# Module.net
KiCad netlist of a schematic drawn in Altium Designer
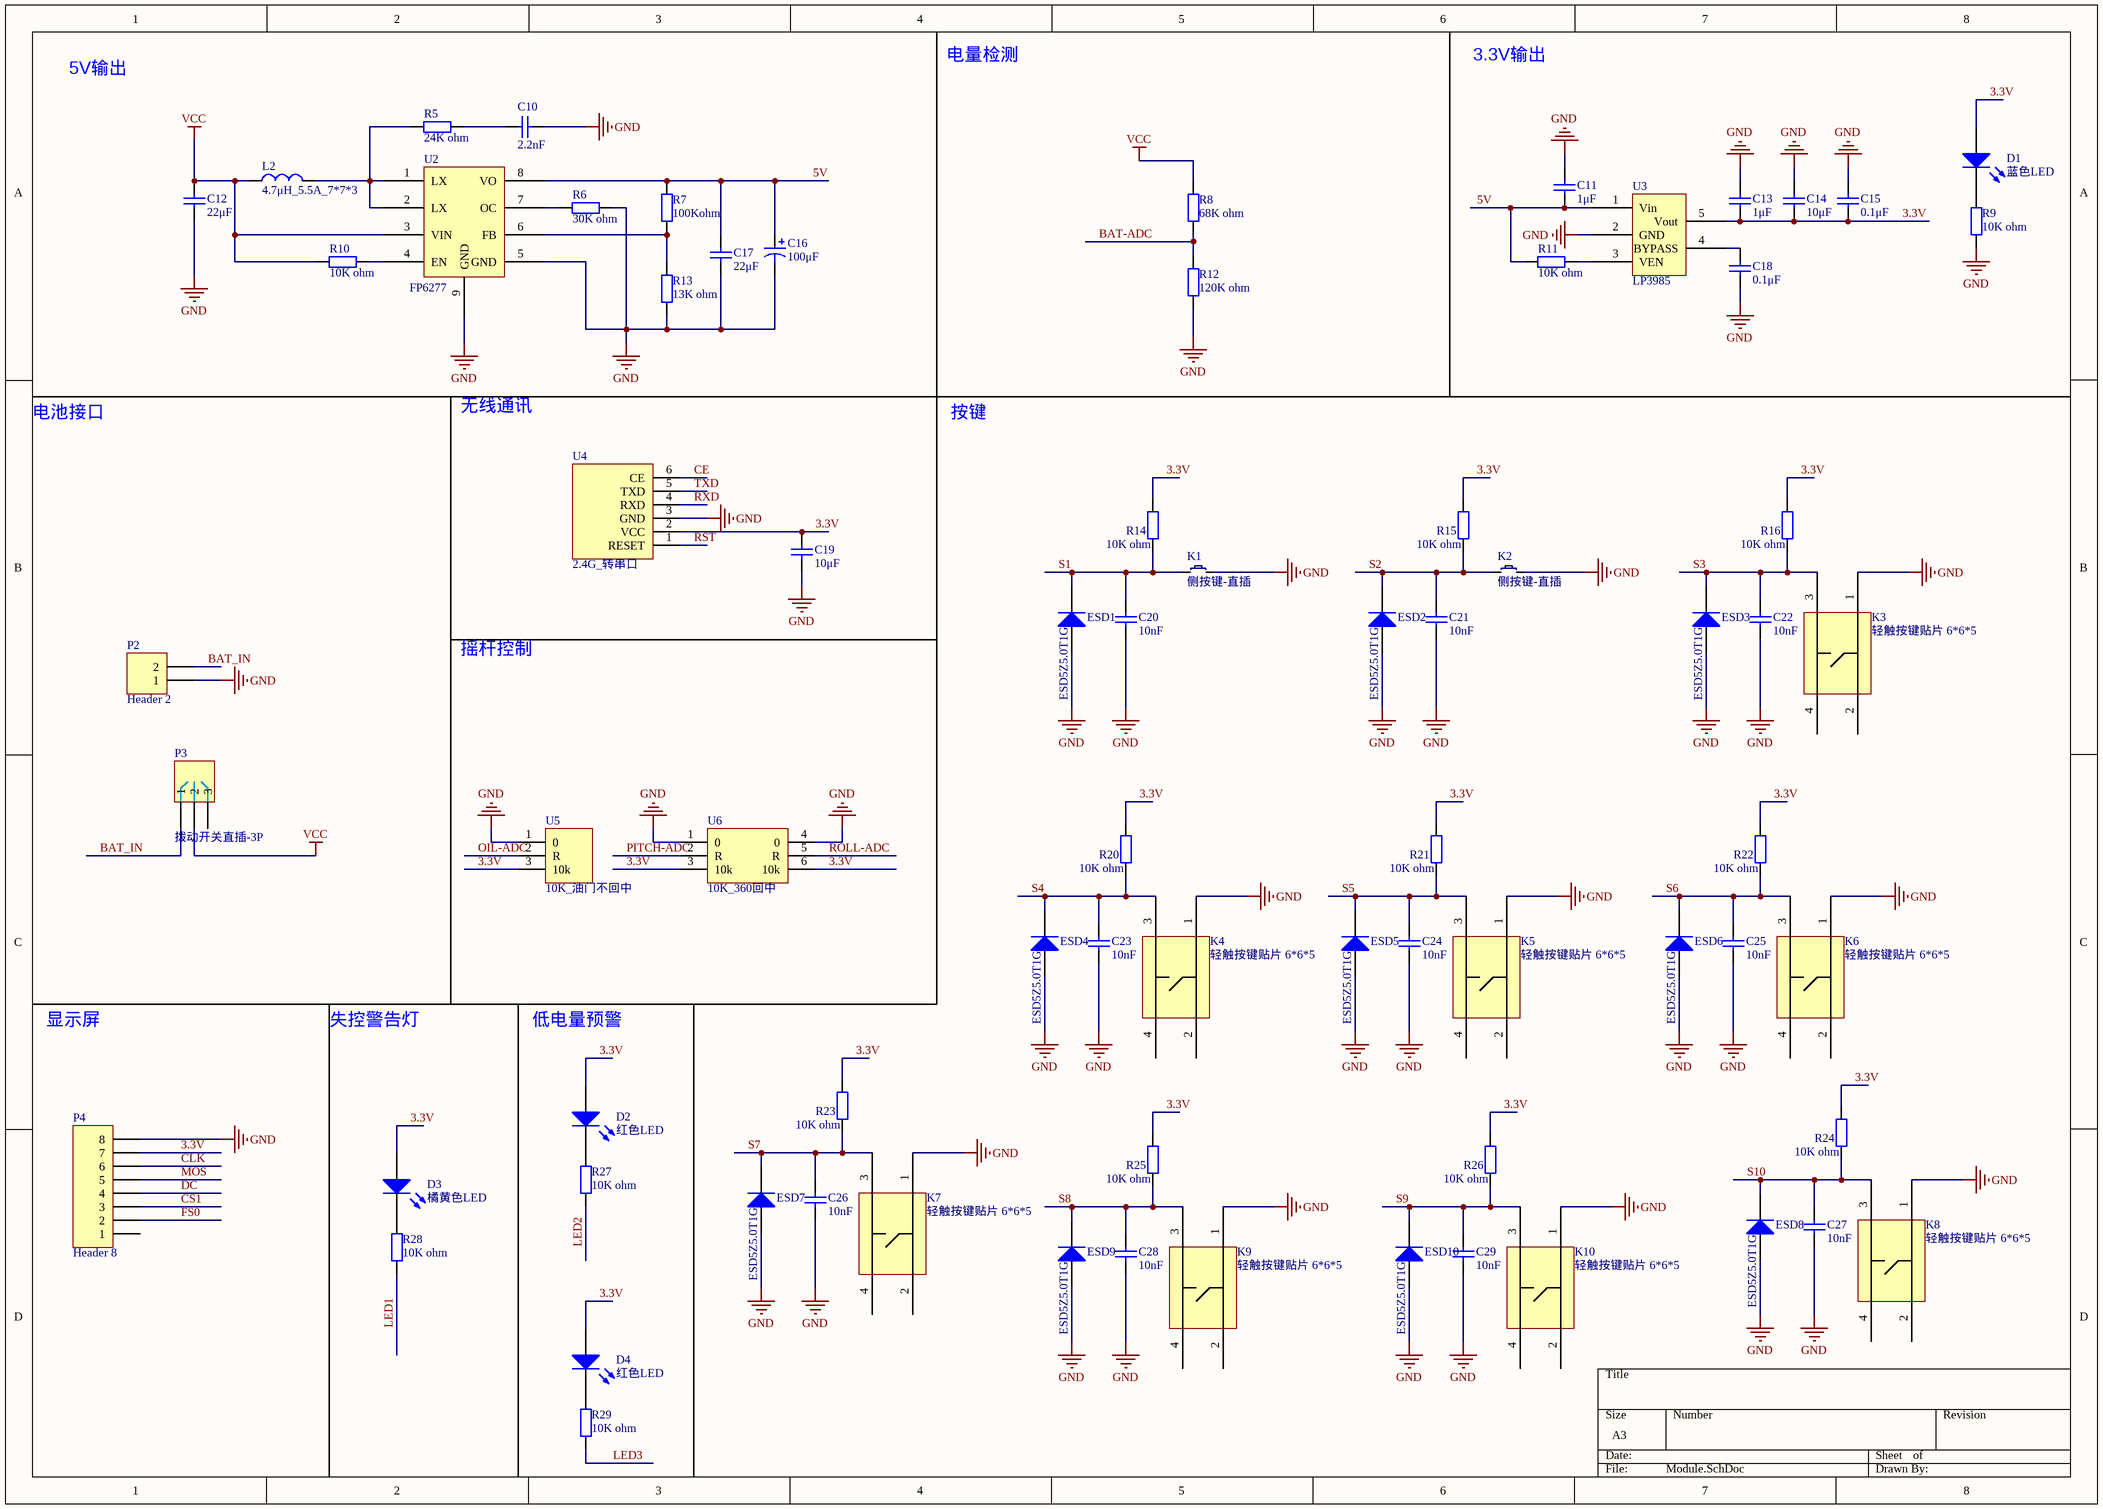
[diagram p0: Module.SchDoc]

(export (version "E")
  (design (tool "Eeschema 10.0.6"))
  (components
    (comp (ref "C10")
      (value "2.2nF")
      (footprint "0603C")
      (description "2.2nF_50V,X7R,10%")
      (libsource (lib "Yang_Lib") (part "Cap_2.2nF_50V_0603"))
    )
    (comp (ref "C11")
      (value "1μF")
      (footprint "0603C")
      (description "1μF_50V,X5R,±10%")
      (libsource (lib "Yang_Lib") (part "Cap_1μF_50V_0603"))
    )
    (comp (ref "C12")
      (value "22μF")
      (footprint "1206C")
      (description "22μF_35V,20%")
      (libsource (lib "Yang_Lib") (part "Cap_22μF_35V_1206"))
    )
    (comp (ref "C13")
      (value "1μF")
      (footprint "0603C")
      (description "1μF_50V,X5R,±10%")
      (libsource (lib "Yang_Lib") (part "Cap_1μF_50V_0603"))
    )
    (comp (ref "C14")
      (value "10μF")
      (footprint "0603C")
      (description "10μF_35V,X5R,20%")
      (libsource (lib "Yang_Lib") (part "Cap_10μF_35V_0603"))
    )
    (comp (ref "C15")
      (value "0.1μF")
      (footprint "0603C")
      (description "0.1μF_50V,X7R,±5%")
      (libsource (lib "Yang_Lib") (part "Cap_0.1μF_50V_0603"))
    )
    (comp (ref "C16")
      (value "100μF")
      (footprint "D7343C")
      (description "100μF_16V")
      (libsource (lib "Yang_Lib") (part "Cap_100μF_16V_D7343"))
    )
    (comp (ref "C17")
      (value "22μF")
      (footprint "1206C")
      (description "22μF_35V,20%")
      (libsource (lib "Yang_Lib") (part "Cap_22μF_35V_1206"))
    )
    (comp (ref "C18")
      (value "0.1μF")
      (footprint "0603C")
      (description "0.1μF_50V,X7R,±5%")
      (libsource (lib "Yang_Lib") (part "Cap_0.1μF_50V_0603"))
    )
    (comp (ref "C19")
      (value "10μF")
      (footprint "0603C")
      (description "10μF_35V,X5R,20%")
      (libsource (lib "Yang_Lib") (part "Cap_10μF_35V_0603"))
    )
    (comp (ref "C20")
      (value "10nF")
      (footprint "0603C")
      (description "10nF_50V,SL_0603,±5%")
      (libsource (lib "Yang_Lib") (part "Cap_10nF_50V_0603"))
    )
    (comp (ref "C21")
      (value "10nF")
      (footprint "0603C")
      (description "10nF_50V,SL_0603,±5%")
      (libsource (lib "Yang_Lib") (part "Cap_10nF_50V_0603"))
    )
    (comp (ref "C22")
      (value "10nF")
      (footprint "0603C")
      (description "10nF_50V,SL_0603,±5%")
      (libsource (lib "Yang_Lib") (part "Cap_10nF_50V_0603"))
    )
    (comp (ref "C23")
      (value "10nF")
      (footprint "0603C")
      (description "10nF_50V,SL_0603,±5%")
      (libsource (lib "Yang_Lib") (part "Cap_10nF_50V_0603"))
    )
    (comp (ref "C24")
      (value "10nF")
      (footprint "0603C")
      (description "10nF_50V,SL_0603,±5%")
      (libsource (lib "Yang_Lib") (part "Cap_10nF_50V_0603"))
    )
    (comp (ref "C25")
      (value "10nF")
      (footprint "0603C")
      (description "10nF_50V,SL_0603,±5%")
      (libsource (lib "Yang_Lib") (part "Cap_10nF_50V_0603"))
    )
    (comp (ref "C26")
      (value "10nF")
      (footprint "0603C")
      (description "10nF_50V,SL_0603,±5%")
      (libsource (lib "Yang_Lib") (part "Cap_10nF_50V_0603"))
    )
    (comp (ref "C27")
      (value "10nF")
      (footprint "0603C")
      (description "10nF_50V,SL_0603,±5%")
      (libsource (lib "Yang_Lib") (part "Cap_10nF_50V_0603"))
    )
    (comp (ref "C28")
      (value "10nF")
      (footprint "0603C")
      (description "10nF_50V,SL_0603,±5%")
      (libsource (lib "Yang_Lib") (part "Cap_10nF_50V_0603"))
    )
    (comp (ref "C29")
      (value "10nF")
      (footprint "0603C")
      (description "10nF_50V,SL_0603,±5%")
      (libsource (lib "Yang_Lib") (part "Cap_10nF_50V_0603"))
    )
    (comp (ref "D1")
      (value "蓝色LED")
      (footprint "Yang_Lib:0603LED")
      (libsource (lib "FSR_BodyLib") (part "蓝色LED"))
    )
    (comp (ref "D2")
      (value "红色LED")
      (footprint "Yang_Lib:0603LED")
      (description "蓝色LED")
      (libsource (lib "FSR_BodyLib") (part "蓝色LED"))
    )
    (comp (ref "D3")
      (value "橘黄色LED")
      (footprint "Yang_Lib:0603LED")
      (description "蓝色LED")
      (libsource (lib "FSR_BodyLib") (part "蓝色LED"))
    )
    (comp (ref "D4")
      (value "红色LED")
      (footprint "Yang_Lib:0603LED")
      (description "蓝色LED")
      (libsource (lib "FSR_BodyLib") (part "蓝色LED"))
    )
    (comp (ref "ESD1")
      (value "ESD5Z5.0T1G")
      (footprint "SOD523")
      (libsource (lib "Yang_Lib") (part "ESD5Z5.0T1G_SOD523"))
    )
    (comp (ref "ESD2")
      (value "ESD5Z5.0T1G")
      (footprint "SOD523")
      (libsource (lib "Yang_Lib") (part "ESD5Z5.0T1G_SOD523"))
    )
    (comp (ref "ESD3")
      (value "ESD5Z5.0T1G")
      (footprint "SOD523")
      (libsource (lib "Yang_Lib") (part "ESD5Z5.0T1G_SOD523"))
    )
    (comp (ref "ESD4")
      (value "ESD5Z5.0T1G")
      (footprint "SOD523")
      (libsource (lib "Yang_Lib") (part "ESD5Z5.0T1G_SOD523"))
    )
    (comp (ref "ESD5")
      (value "ESD5Z5.0T1G")
      (footprint "SOD523")
      (libsource (lib "Yang_Lib") (part "ESD5Z5.0T1G_SOD523"))
    )
    (comp (ref "ESD6")
      (value "ESD5Z5.0T1G")
      (footprint "SOD523")
      (libsource (lib "Yang_Lib") (part "ESD5Z5.0T1G_SOD523"))
    )
    (comp (ref "ESD7")
      (value "ESD5Z5.0T1G")
      (footprint "SOD523")
      (libsource (lib "Yang_Lib") (part "ESD5Z5.0T1G_SOD523"))
    )
    (comp (ref "ESD8")
      (value "ESD5Z5.0T1G")
      (footprint "SOD523")
      (libsource (lib "Yang_Lib") (part "ESD5Z5.0T1G_SOD523"))
    )
    (comp (ref "ESD9")
      (value "ESD5Z5.0T1G")
      (footprint "SOD523")
      (libsource (lib "Yang_Lib") (part "ESD5Z5.0T1G_SOD523"))
    )
    (comp (ref "ESD10")
      (value "ESD5Z5.0T1G")
      (footprint "SOD523")
      (libsource (lib "Yang_Lib") (part "ESD5Z5.0T1G_SOD523"))
    )
    (comp (ref "K1") (value "侧按键-直插") (footprint "侧按键-直插") (libsource (lib "Yang_Lib") (part "侧按键-直插")))
    (comp (ref "K2") (value "侧按键-直插") (footprint "侧按键-直插") (libsource (lib "Yang_Lib") (part "侧按键-直插")))
    (comp (ref "K3")
      (value "轻触按键贴片 6*6*5")
      (footprint "轻触按键贴片 6*6*5")
      (libsource (lib "Yang_Lib") (part "轻触按键贴片 6*6*5"))
    )
    (comp (ref "K4")
      (value "轻触按键贴片 6*6*5")
      (footprint "轻触按键贴片 6*6*5")
      (libsource (lib "Yang_Lib") (part "轻触按键贴片 6*6*5"))
    )
    (comp (ref "K5")
      (value "轻触按键贴片 6*6*5")
      (footprint "轻触按键贴片 6*6*5")
      (libsource (lib "Yang_Lib") (part "轻触按键贴片 6*6*5"))
    )
    (comp (ref "K6")
      (value "轻触按键贴片 6*6*5")
      (footprint "轻触按键贴片 6*6*5")
      (libsource (lib "Yang_Lib") (part "轻触按键贴片 6*6*5"))
    )
    (comp (ref "K7")
      (value "轻触按键贴片 6*6*5")
      (footprint "轻触按键贴片 6*6*5")
      (libsource (lib "Yang_Lib") (part "轻触按键贴片 6*6*5"))
    )
    (comp (ref "K8")
      (value "轻触按键贴片 6*6*5")
      (footprint "轻触按键贴片 6*6*5")
      (libsource (lib "Yang_Lib") (part "轻触按键贴片 6*6*5"))
    )
    (comp (ref "K9")
      (value "轻触按键贴片 6*6*5")
      (footprint "轻触按键贴片 6*6*5")
      (libsource (lib "Yang_Lib") (part "轻触按键贴片 6*6*5"))
    )
    (comp (ref "K10")
      (value "轻触按键贴片 6*6*5")
      (footprint "轻触按键贴片 6*6*5")
      (libsource (lib "Yang_Lib") (part "轻触按键贴片 6*6*5"))
    )
    (comp (ref "L2")
      (value "4.7μH_5.5A_7*7*3")
      (footprint "7*7*3mm - 06030")
      (description "4.7μH_5.5A_")
      (libsource (lib "Yang_Lib") (part "4.7μH_5.5A_7*7*3"))
    )
    (comp (ref "P2")
      (value "Header 2")
      (footprint "HDR1X2")
      (description "Header, 2-Pin")
      (fields (field (name "PUBLISHER") "Altium Limited"))
      (libsource (lib "Miscellaneous Connectors") (part "Header 2"))
    )
    (comp (ref "P3")
      (value "拨动开关直插-3P")
      (footprint "拨动开关-3P")
      (libsource (lib "Yang_Lib") (part "拨动开关直插-3P"))
    )
    (comp (ref "P4")
      (value "Header 8")
      (footprint "HDR1X8")
      (description "Header, 8-Pin")
      (fields (field (name "PUBLISHER") "Altium Limited"))
      (libsource (lib "Miscellaneous Connectors") (part "Header 8"))
    )
    (comp (ref "R5")
      (value "24K ohm")
      (footprint "0603R")
      (description "24K ohm,1%")
      (libsource (lib "Yang_Lib") (part "Res_24K ohm_0603"))
    )
    (comp (ref "R6")
      (value "30K ohm")
      (footprint "0603R")
      (description "30K ohm,1%")
      (libsource (lib "Yang_Lib") (part "Res_30K ohm_0603"))
    )
    (comp (ref "R7")
      (value "100Kohm")
      (footprint "0603R")
      (description "100K ohm_5%")
      (libsource (lib "Yang_Lib") (part "Res_100Kohm_0603"))
    )
    (comp (ref "R8")
      (value "68K ohm")
      (footprint "0603R")
      (description "68K ohm,1%")
      (libsource (lib "Yang_Lib") (part "Res_68K ohm_0603"))
    )
    (comp (ref "R9")
      (value "10K ohm")
      (footprint "Yang_Lib:0603R")
      (description "10K ohm,1%")
      (libsource (lib "FSR_BodyLib") (part "Res_10K ohm_0603"))
    )
    (comp (ref "R10")
      (value "10K ohm")
      (footprint "0603R")
      (description "10K ohm,1%")
      (libsource (lib "Yang_Lib") (part "Res_10K ohm_0603"))
    )
    (comp (ref "R11")
      (value "10K ohm")
      (footprint "0603R")
      (description "10K ohm,1%")
      (libsource (lib "Yang_Lib") (part "Res_10K ohm_0603"))
    )
    (comp (ref "R12")
      (value "120K ohm")
      (footprint "0603R")
      (description "120K ohm,1%")
      (libsource (lib "Yang_Lib") (part "Res_120K ohm_0603"))
    )
    (comp (ref "R13")
      (value "13K ohm")
      (footprint "0603R")
      (description "13K ohm,1%")
      (libsource (lib "Yang_Lib") (part "Res_13K ohm_0603"))
    )
    (comp (ref "R14")
      (value "10K ohm")
      (footprint "0603R")
      (description "10K ohm,1%")
      (libsource (lib "") (part "Res_10K ohm_0603_1"))
    )
    (comp (ref "R15")
      (value "10K ohm")
      (footprint "0603R")
      (description "10K ohm,1%")
      (libsource (lib "") (part "Res_10K ohm_0603_1"))
    )
    (comp (ref "R16")
      (value "10K ohm")
      (footprint "0603R")
      (description "10K ohm,1%")
      (libsource (lib "") (part "Res_10K ohm_0603_1"))
    )
    (comp (ref "R20")
      (value "10K ohm")
      (footprint "0603R")
      (description "10K ohm,1%")
      (libsource (lib "") (part "Res_10K ohm_0603_1"))
    )
    (comp (ref "R21")
      (value "10K ohm")
      (footprint "0603R")
      (description "10K ohm,1%")
      (libsource (lib "") (part "Res_10K ohm_0603_1"))
    )
    (comp (ref "R22")
      (value "10K ohm")
      (footprint "0603R")
      (description "10K ohm,1%")
      (libsource (lib "") (part "Res_10K ohm_0603_1"))
    )
    (comp (ref "R23")
      (value "10K ohm")
      (footprint "0603R")
      (description "10K ohm,1%")
      (libsource (lib "") (part "Res_10K ohm_0603_1"))
    )
    (comp (ref "R24")
      (value "10K ohm")
      (footprint "0603R")
      (description "10K ohm,1%")
      (libsource (lib "") (part "Res_10K ohm_0603_1"))
    )
    (comp (ref "R25")
      (value "10K ohm")
      (footprint "0603R")
      (description "10K ohm,1%")
      (libsource (lib "") (part "Res_10K ohm_0603_1"))
    )
    (comp (ref "R26")
      (value "10K ohm")
      (footprint "0603R")
      (description "10K ohm,1%")
      (libsource (lib "") (part "Res_10K ohm_0603_1"))
    )
    (comp (ref "R27")
      (value "10K ohm")
      (footprint "Yang_Lib:0603R")
      (description "10K ohm,1%")
      (libsource (lib "FSR_BodyLib") (part "Res_10K ohm_0603"))
    )
    (comp (ref "R28")
      (value "10K ohm")
      (footprint "Yang_Lib:0603R")
      (description "10K ohm,1%")
      (libsource (lib "FSR_BodyLib") (part "Res_10K ohm_0603"))
    )
    (comp (ref "R29")
      (value "10K ohm")
      (footprint "Yang_Lib:0603R")
      (description "10K ohm,1%")
      (libsource (lib "FSR_BodyLib") (part "Res_10K ohm_0603"))
    )
    (comp (ref "U2") (value "FP6277") (footprint "SO8 - FP6277") (libsource (lib "Yang_Lib") (part "FP6277")))
    (comp (ref "U3") (value "LP3985") (footprint "SOT-23-5") (libsource (lib "Yang_Lib") (part "LP3985")))
    (comp (ref "U4") (value "2.4G_转串口") (footprint "2.4G-串口") (libsource (lib "Yang_Lib") (part "2.4G_转串口")))
    (comp (ref "U5")
      (value "10K_油门不回中")
      (footprint "10K_油门不回中")
      (libsource (lib "Yang_Lib") (part "10K_油门不回中"))
    )
    (comp (ref "U6")
      (value "10K_360回中")
      (footprint "10K_360回中")
      (libsource (lib "Yang_Lib") (part "10K_360回中"))
    )
  )
  (nets
    (net (code "1") (name "/3.3V") (class "Default")
      (node (ref "C13") (pin "2") (pinfunction "2_2") (pintype "passive"))
      (node (ref "C14") (pin "1") (pinfunction "1_1") (pintype "passive"))
      (node (ref "C15") (pin "1") (pinfunction "1_1") (pintype "passive"))
      (node (ref "C19") (pin "2") (pinfunction "2_2") (pintype "passive"))
      (node (ref "D1") (pin "1") (pinfunction "A_1") (pintype "passive"))
      (node (ref "D2") (pin "1") (pinfunction "A_1") (pintype "passive"))
      (node (ref "D3") (pin "1") (pinfunction "A_1") (pintype "passive"))
      (node (ref "D4") (pin "1") (pinfunction "A_1") (pintype "passive"))
      (node (ref "P4") (pin "7") (pinfunction "7_7") (pintype "passive"))
      (node (ref "R14") (pin "2") (pinfunction "2_2") (pintype "passive"))
      (node (ref "R15") (pin "2") (pinfunction "2_2") (pintype "passive"))
      (node (ref "R16") (pin "2") (pinfunction "2_2") (pintype "passive"))
      (node (ref "R20") (pin "2") (pinfunction "2_2") (pintype "passive"))
      (node (ref "R21") (pin "2") (pinfunction "2_2") (pintype "passive"))
      (node (ref "R22") (pin "2") (pinfunction "2_2") (pintype "passive"))
      (node (ref "R23") (pin "2") (pinfunction "2_2") (pintype "passive"))
      (node (ref "R24") (pin "2") (pinfunction "2_2") (pintype "passive"))
      (node (ref "R25") (pin "2") (pinfunction "2_2") (pintype "passive"))
      (node (ref "R26") (pin "2") (pinfunction "2_2") (pintype "passive"))
      (node (ref "U3") (pin "5") (pinfunction "Vout_5") (pintype "passive"))
      (node (ref "U4") (pin "2") (pinfunction "VCC_2") (pintype "passive"))
      (node (ref "U5") (pin "3") (pinfunction "10k_3") (pintype "passive"))
      (node (ref "U6") (pin "3") (pinfunction "10k_3") (pintype "passive"))
      (node (ref "U6") (pin "6") (pinfunction "10k_6") (pintype "passive"))
    )
    (net (code "2") (name "/5V") (class "Default")
      (node (ref "C11") (pin "2") (pinfunction "2_2") (pintype "passive"))
      (node (ref "C16") (pin "1") (pinfunction "1_1") (pintype "passive"))
      (node (ref "C17") (pin "2") (pinfunction "2_2") (pintype "passive"))
      (node (ref "R11") (pin "1") (pinfunction "1_1") (pintype "passive"))
      (node (ref "R7") (pin "2") (pinfunction "2_2") (pintype "passive"))
      (node (ref "U2") (pin "8") (pinfunction "VO_8") (pintype "passive"))
      (node (ref "U3") (pin "1") (pinfunction "Vin_1") (pintype "passive"))
    )
    (net (code "3") (name "/BAT-ADC") (class "Default")
      (node (ref "R12") (pin "2") (pinfunction "2_2") (pintype "passive"))
      (node (ref "R8") (pin "1") (pinfunction "1_1") (pintype "passive"))
    )
    (net (code "4") (name "/BAT_IN") (class "Default")
      (node (ref "P2") (pin "2") (pinfunction "2_2") (pintype "passive"))
      (node (ref "P3") (pin "1") (pinfunction "1_1") (pintype "passive"))
    )
    (net (code "5") (name "/CE") (class "Default")
      (node (ref "U4") (pin "6") (pinfunction "CE_6") (pintype "passive"))
    )
    (net (code "6") (name "/CLK") (class "Default")
      (node (ref "P4") (pin "6") (pinfunction "6_6") (pintype "passive"))
    )
    (net (code "7") (name "/CS1") (class "Default")
      (node (ref "P4") (pin "3") (pinfunction "3_3") (pintype "passive"))
    )
    (net (code "8") (name "/DC") (class "Default")
      (node (ref "P4") (pin "4") (pinfunction "4_4") (pintype "passive"))
    )
    (net (code "9") (name "/FS0") (class "Default")
      (node (ref "P4") (pin "2") (pinfunction "2_2") (pintype "passive"))
    )
    (net (code "10") (name "/LED1") (class "Default")
      (node (ref "R28") (pin "1") (pinfunction "1_1") (pintype "passive"))
    )
    (net (code "11") (name "/LED2") (class "Default")
      (node (ref "R27") (pin "1") (pinfunction "1_1") (pintype "passive"))
    )
    (net (code "12") (name "/LED3") (class "Default")
      (node (ref "R29") (pin "1") (pinfunction "1_1") (pintype "passive"))
    )
    (net (code "13") (name "/MOS") (class "Default")
      (node (ref "P4") (pin "5") (pinfunction "5_5") (pintype "passive"))
    )
    (net (code "14") (name "/OIL-ADC") (class "Default")
      (node (ref "U5") (pin "2") (pinfunction "R_2") (pintype "passive"))
    )
    (net (code "15") (name "/PITCH-ADC") (class "Default")
      (node (ref "U6") (pin "2") (pinfunction "R_2") (pintype "passive"))
    )
    (net (code "16") (name "/ROLL-ADC") (class "Default")
      (node (ref "U6") (pin "5") (pinfunction "R_5") (pintype "passive"))
    )
    (net (code "17") (name "/RST") (class "Default")
      (node (ref "U4") (pin "1") (pinfunction "RESET_1") (pintype "passive"))
    )
    (net (code "18") (name "/RXD") (class "Default")
      (node (ref "U4") (pin "4") (pinfunction "RXD_4") (pintype "passive"))
    )
    (net (code "19") (name "/S1") (class "Default")
      (node (ref "C20") (pin "1") (pinfunction "1_1") (pintype "passive"))
      (node (ref "ESD1") (pin "2") (pinfunction "K_2") (pintype "passive"))
      (node (ref "K1") (pin "1") (pinfunction "1_1") (pintype "passive"))
      (node (ref "R14") (pin "1") (pinfunction "1_1") (pintype "passive"))
    )
    (net (code "20") (name "/S2") (class "Default")
      (node (ref "C21") (pin "1") (pinfunction "1_1") (pintype "passive"))
      (node (ref "ESD2") (pin "2") (pinfunction "K_2") (pintype "passive"))
      (node (ref "K2") (pin "1") (pinfunction "1_1") (pintype "passive"))
      (node (ref "R15") (pin "1") (pinfunction "1_1") (pintype "passive"))
    )
    (net (code "21") (name "/S3") (class "Default")
      (node (ref "C22") (pin "1") (pinfunction "1_1") (pintype "passive"))
      (node (ref "ESD3") (pin "2") (pinfunction "K_2") (pintype "passive"))
      (node (ref "K3") (pin "3") (pinfunction "3_3") (pintype "passive"))
      (node (ref "R16") (pin "1") (pinfunction "1_1") (pintype "passive"))
    )
    (net (code "22") (name "/S4") (class "Default")
      (node (ref "C23") (pin "1") (pinfunction "1_1") (pintype "passive"))
      (node (ref "ESD4") (pin "2") (pinfunction "K_2") (pintype "passive"))
      (node (ref "K4") (pin "3") (pinfunction "3_3") (pintype "passive"))
      (node (ref "R20") (pin "1") (pinfunction "1_1") (pintype "passive"))
    )
    (net (code "23") (name "/S5") (class "Default")
      (node (ref "C24") (pin "1") (pinfunction "1_1") (pintype "passive"))
      (node (ref "ESD5") (pin "2") (pinfunction "K_2") (pintype "passive"))
      (node (ref "K5") (pin "3") (pinfunction "3_3") (pintype "passive"))
      (node (ref "R21") (pin "1") (pinfunction "1_1") (pintype "passive"))
    )
    (net (code "24") (name "/S6") (class "Default")
      (node (ref "C25") (pin "1") (pinfunction "1_1") (pintype "passive"))
      (node (ref "ESD6") (pin "2") (pinfunction "K_2") (pintype "passive"))
      (node (ref "K6") (pin "3") (pinfunction "3_3") (pintype "passive"))
      (node (ref "R22") (pin "1") (pinfunction "1_1") (pintype "passive"))
    )
    (net (code "25") (name "/S7") (class "Default")
      (node (ref "C26") (pin "1") (pinfunction "1_1") (pintype "passive"))
      (node (ref "ESD7") (pin "2") (pinfunction "K_2") (pintype "passive"))
      (node (ref "K7") (pin "3") (pinfunction "3_3") (pintype "passive"))
      (node (ref "R23") (pin "1") (pinfunction "1_1") (pintype "passive"))
    )
    (net (code "26") (name "/S8") (class "Default")
      (node (ref "C28") (pin "1") (pinfunction "1_1") (pintype "passive"))
      (node (ref "ESD9") (pin "2") (pinfunction "K_2") (pintype "passive"))
      (node (ref "K9") (pin "3") (pinfunction "3_3") (pintype "passive"))
      (node (ref "R25") (pin "1") (pinfunction "1_1") (pintype "passive"))
    )
    (net (code "27") (name "/S9") (class "Default")
      (node (ref "C29") (pin "1") (pinfunction "1_1") (pintype "passive"))
      (node (ref "ESD10") (pin "2") (pinfunction "K_2") (pintype "passive"))
      (node (ref "K10") (pin "3") (pinfunction "3_3") (pintype "passive"))
      (node (ref "R26") (pin "1") (pinfunction "1_1") (pintype "passive"))
    )
    (net (code "28") (name "/S10") (class "Default")
      (node (ref "C27") (pin "1") (pinfunction "1_1") (pintype "passive"))
      (node (ref "ESD8") (pin "2") (pinfunction "K_2") (pintype "passive"))
      (node (ref "K8") (pin "3") (pinfunction "3_3") (pintype "passive"))
      (node (ref "R24") (pin "1") (pinfunction "1_1") (pintype "passive"))
    )
    (net (code "29") (name "/TXD") (class "Default")
      (node (ref "U4") (pin "5") (pinfunction "TXD_5") (pintype "passive"))
    )
    (net (code "30") (name "GND") (class "Default")
      (node (ref "C10") (pin "1") (pinfunction "1_1") (pintype "passive"))
      (node (ref "C11") (pin "1") (pinfunction "1_1") (pintype "passive"))
      (node (ref "C12") (pin "1") (pinfunction "1_1") (pintype "passive"))
      (node (ref "C13") (pin "1") (pinfunction "1_1") (pintype "passive"))
      (node (ref "C14") (pin "2") (pinfunction "2_2") (pintype "passive"))
      (node (ref "C15") (pin "2") (pinfunction "2_2") (pintype "passive"))
      (node (ref "C16") (pin "2") (pinfunction "2_2") (pintype "passive"))
      (node (ref "C17") (pin "1") (pinfunction "1_1") (pintype "passive"))
      (node (ref "C18") (pin "1") (pinfunction "1_1") (pintype "passive"))
      (node (ref "C19") (pin "1") (pinfunction "1_1") (pintype "passive"))
      (node (ref "C20") (pin "2") (pinfunction "2_2") (pintype "passive"))
      (node (ref "C21") (pin "2") (pinfunction "2_2") (pintype "passive"))
      (node (ref "C22") (pin "2") (pinfunction "2_2") (pintype "passive"))
      (node (ref "C23") (pin "2") (pinfunction "2_2") (pintype "passive"))
      (node (ref "C24") (pin "2") (pinfunction "2_2") (pintype "passive"))
      (node (ref "C25") (pin "2") (pinfunction "2_2") (pintype "passive"))
      (node (ref "C26") (pin "2") (pinfunction "2_2") (pintype "passive"))
      (node (ref "C27") (pin "2") (pinfunction "2_2") (pintype "passive"))
      (node (ref "C28") (pin "2") (pinfunction "2_2") (pintype "passive"))
      (node (ref "C29") (pin "2") (pinfunction "2_2") (pintype "passive"))
      (node (ref "ESD1") (pin "1") (pinfunction "A_1") (pintype "passive"))
      (node (ref "ESD10") (pin "1") (pinfunction "A_1") (pintype "passive"))
      (node (ref "ESD2") (pin "1") (pinfunction "A_1") (pintype "passive"))
      (node (ref "ESD3") (pin "1") (pinfunction "A_1") (pintype "passive"))
      (node (ref "ESD4") (pin "1") (pinfunction "A_1") (pintype "passive"))
      (node (ref "ESD5") (pin "1") (pinfunction "A_1") (pintype "passive"))
      (node (ref "ESD6") (pin "1") (pinfunction "A_1") (pintype "passive"))
      (node (ref "ESD7") (pin "1") (pinfunction "A_1") (pintype "passive"))
      (node (ref "ESD8") (pin "1") (pinfunction "A_1") (pintype "passive"))
      (node (ref "ESD9") (pin "1") (pinfunction "A_1") (pintype "passive"))
      (node (ref "K1") (pin "2") (pinfunction "2_2") (pintype "passive"))
      (node (ref "K10") (pin "1") (pinfunction "1_1") (pintype "passive"))
      (node (ref "K2") (pin "2") (pinfunction "2_2") (pintype "passive"))
      (node (ref "K3") (pin "1") (pinfunction "1_1") (pintype "passive"))
      (node (ref "K4") (pin "1") (pinfunction "1_1") (pintype "passive"))
      (node (ref "K5") (pin "1") (pinfunction "1_1") (pintype "passive"))
      (node (ref "K6") (pin "1") (pinfunction "1_1") (pintype "passive"))
      (node (ref "K7") (pin "1") (pinfunction "1_1") (pintype "passive"))
      (node (ref "K8") (pin "1") (pinfunction "1_1") (pintype "passive"))
      (node (ref "K9") (pin "1") (pinfunction "1_1") (pintype "passive"))
      (node (ref "P2") (pin "1") (pinfunction "1_1") (pintype "passive"))
      (node (ref "P4") (pin "8") (pinfunction "8_8") (pintype "passive"))
      (node (ref "R12") (pin "1") (pinfunction "1_1") (pintype "passive"))
      (node (ref "R13") (pin "1") (pinfunction "1_1") (pintype "passive"))
      (node (ref "R6") (pin "2") (pinfunction "2_2") (pintype "passive"))
      (node (ref "R9") (pin "1") (pinfunction "1_1") (pintype "passive"))
      (node (ref "U2") (pin "5") (pinfunction "GND_5") (pintype "passive"))
      (node (ref "U2") (pin "9") (pinfunction "GND_9") (pintype "passive"))
      (node (ref "U3") (pin "2") (pinfunction "GND_2") (pintype "passive"))
      (node (ref "U4") (pin "3") (pinfunction "GND_3") (pintype "passive"))
      (node (ref "U5") (pin "1") (pinfunction "0_1") (pintype "passive"))
      (node (ref "U6") (pin "1") (pinfunction "0_1") (pintype "passive"))
      (node (ref "U6") (pin "4") (pinfunction "0_4") (pintype "passive"))
    )
    (net (code "31") (name "Net-(C10-Pad2)") (class "Default")
      (node (ref "C10") (pin "2") (pinfunction "2_2") (pintype "passive"))
      (node (ref "R5") (pin "1") (pinfunction "1_1") (pintype "passive"))
    )
    (net (code "32") (name "Net-(D1-K)") (class "Default")
      (node (ref "D1") (pin "2") (pinfunction "K_2") (pintype "passive"))
      (node (ref "R9") (pin "2") (pinfunction "2_2") (pintype "passive"))
    )
    (net (code "33") (name "Net-(D2-K)") (class "Default")
      (node (ref "D2") (pin "2") (pinfunction "K_2") (pintype "passive"))
      (node (ref "R27") (pin "2") (pinfunction "2_2") (pintype "passive"))
    )
    (net (code "34") (name "Net-(D3-K)") (class "Default")
      (node (ref "D3") (pin "2") (pinfunction "K_2") (pintype "passive"))
      (node (ref "R28") (pin "2") (pinfunction "2_2") (pintype "passive"))
    )
    (net (code "35") (name "Net-(D4-K)") (class "Default")
      (node (ref "D4") (pin "2") (pinfunction "K_2") (pintype "passive"))
      (node (ref "R29") (pin "2") (pinfunction "2_2") (pintype "passive"))
    )
    (net (code "36") (name "Net-(L2-Pad2)") (class "Default")
      (node (ref "L2") (pin "2") (pinfunction "2_2") (pintype "passive"))
      (node (ref "R5") (pin "2") (pinfunction "2_2") (pintype "passive"))
      (node (ref "U2") (pin "1") (pinfunction "LX_1") (pintype "passive"))
      (node (ref "U2") (pin "2") (pinfunction "LX_2") (pintype "passive"))
    )
    (net (code "37") (name "Net-(U2-EN)") (class "Default")
      (node (ref "R10") (pin "2") (pinfunction "2_2") (pintype "passive"))
      (node (ref "U2") (pin "4") (pinfunction "EN_4") (pintype "passive"))
    )
    (net (code "38") (name "Net-(U2-FB)") (class "Default")
      (node (ref "R13") (pin "2") (pinfunction "2_2") (pintype "passive"))
      (node (ref "R7") (pin "1") (pinfunction "1_1") (pintype "passive"))
      (node (ref "U2") (pin "6") (pinfunction "FB_6") (pintype "passive"))
    )
    (net (code "39") (name "Net-(U2-OC)") (class "Default")
      (node (ref "R6") (pin "1") (pinfunction "1_1") (pintype "passive"))
      (node (ref "U2") (pin "7") (pinfunction "OC_7") (pintype "passive"))
    )
    (net (code "40") (name "Net-(U3-BYPASS)") (class "Default")
      (node (ref "C18") (pin "2") (pinfunction "2_2") (pintype "passive"))
      (node (ref "U3") (pin "4") (pinfunction "BYPASS_4") (pintype "passive"))
    )
    (net (code "41") (name "Net-(U3-VEN)") (class "Default")
      (node (ref "R11") (pin "2") (pinfunction "2_2") (pintype "passive"))
      (node (ref "U3") (pin "3") (pinfunction "VEN_3") (pintype "passive"))
    )
    (net (code "42") (name "VCC") (class "Default")
      (node (ref "C12") (pin "2") (pinfunction "2_2") (pintype "passive"))
      (node (ref "L2") (pin "1") (pinfunction "1_1") (pintype "passive"))
      (node (ref "P3") (pin "2") (pinfunction "2_2") (pintype "passive"))
      (node (ref "R10") (pin "1") (pinfunction "1_1") (pintype "passive"))
      (node (ref "R8") (pin "2") (pinfunction "2_2") (pintype "passive"))
      (node (ref "U2") (pin "3") (pinfunction "VIN_3") (pintype "passive"))
    )
    (net (code "43") (name "unconnected-(K3-Pad2)") (class "Default")
      (node (ref "K3") (pin "2") (pinfunction "2_2") (pintype "passive"))
    )
    (net (code "44") (name "unconnected-(K3-Pad4)") (class "Default")
      (node (ref "K3") (pin "4") (pinfunction "4_4") (pintype "passive"))
    )
    (net (code "45") (name "unconnected-(K4-Pad2)") (class "Default")
      (node (ref "K4") (pin "2") (pinfunction "2_2") (pintype "passive"))
    )
    (net (code "46") (name "unconnected-(K4-Pad4)") (class "Default")
      (node (ref "K4") (pin "4") (pinfunction "4_4") (pintype "passive"))
    )
    (net (code "47") (name "unconnected-(K5-Pad2)") (class "Default")
      (node (ref "K5") (pin "2") (pinfunction "2_2") (pintype "passive"))
    )
    (net (code "48") (name "unconnected-(K5-Pad4)") (class "Default")
      (node (ref "K5") (pin "4") (pinfunction "4_4") (pintype "passive"))
    )
    (net (code "49") (name "unconnected-(K6-Pad2)") (class "Default")
      (node (ref "K6") (pin "2") (pinfunction "2_2") (pintype "passive"))
    )
    (net (code "50") (name "unconnected-(K6-Pad4)") (class "Default")
      (node (ref "K6") (pin "4") (pinfunction "4_4") (pintype "passive"))
    )
    (net (code "51") (name "unconnected-(K7-Pad2)") (class "Default")
      (node (ref "K7") (pin "2") (pinfunction "2_2") (pintype "passive"))
    )
    (net (code "52") (name "unconnected-(K7-Pad4)") (class "Default")
      (node (ref "K7") (pin "4") (pinfunction "4_4") (pintype "passive"))
    )
    (net (code "53") (name "unconnected-(K8-Pad2)") (class "Default")
      (node (ref "K8") (pin "2") (pinfunction "2_2") (pintype "passive"))
    )
    (net (code "54") (name "unconnected-(K8-Pad4)") (class "Default")
      (node (ref "K8") (pin "4") (pinfunction "4_4") (pintype "passive"))
    )
    (net (code "55") (name "unconnected-(K9-Pad2)") (class "Default")
      (node (ref "K9") (pin "2") (pinfunction "2_2") (pintype "passive"))
    )
    (net (code "56") (name "unconnected-(K9-Pad4)") (class "Default")
      (node (ref "K9") (pin "4") (pinfunction "4_4") (pintype "passive"))
    )
    (net (code "57") (name "unconnected-(K10-Pad2)") (class "Default")
      (node (ref "K10") (pin "2") (pinfunction "2_2") (pintype "passive"))
    )
    (net (code "58") (name "unconnected-(K10-Pad4)") (class "Default")
      (node (ref "K10") (pin "4") (pinfunction "4_4") (pintype "passive"))
    )
    (net (code "59") (name "unconnected-(P3-Pad3)") (class "Default")
      (node (ref "P3") (pin "3") (pinfunction "3_3") (pintype "passive"))
    )
    (net (code "60") (name "unconnected-(P4-Pad1)") (class "Default")
      (node (ref "P4") (pin "1") (pinfunction "1_1") (pintype "passive"))
    )
  )
)
